# de1_breakout.net
KiCad netlist of a schematic drawn in EAGLE
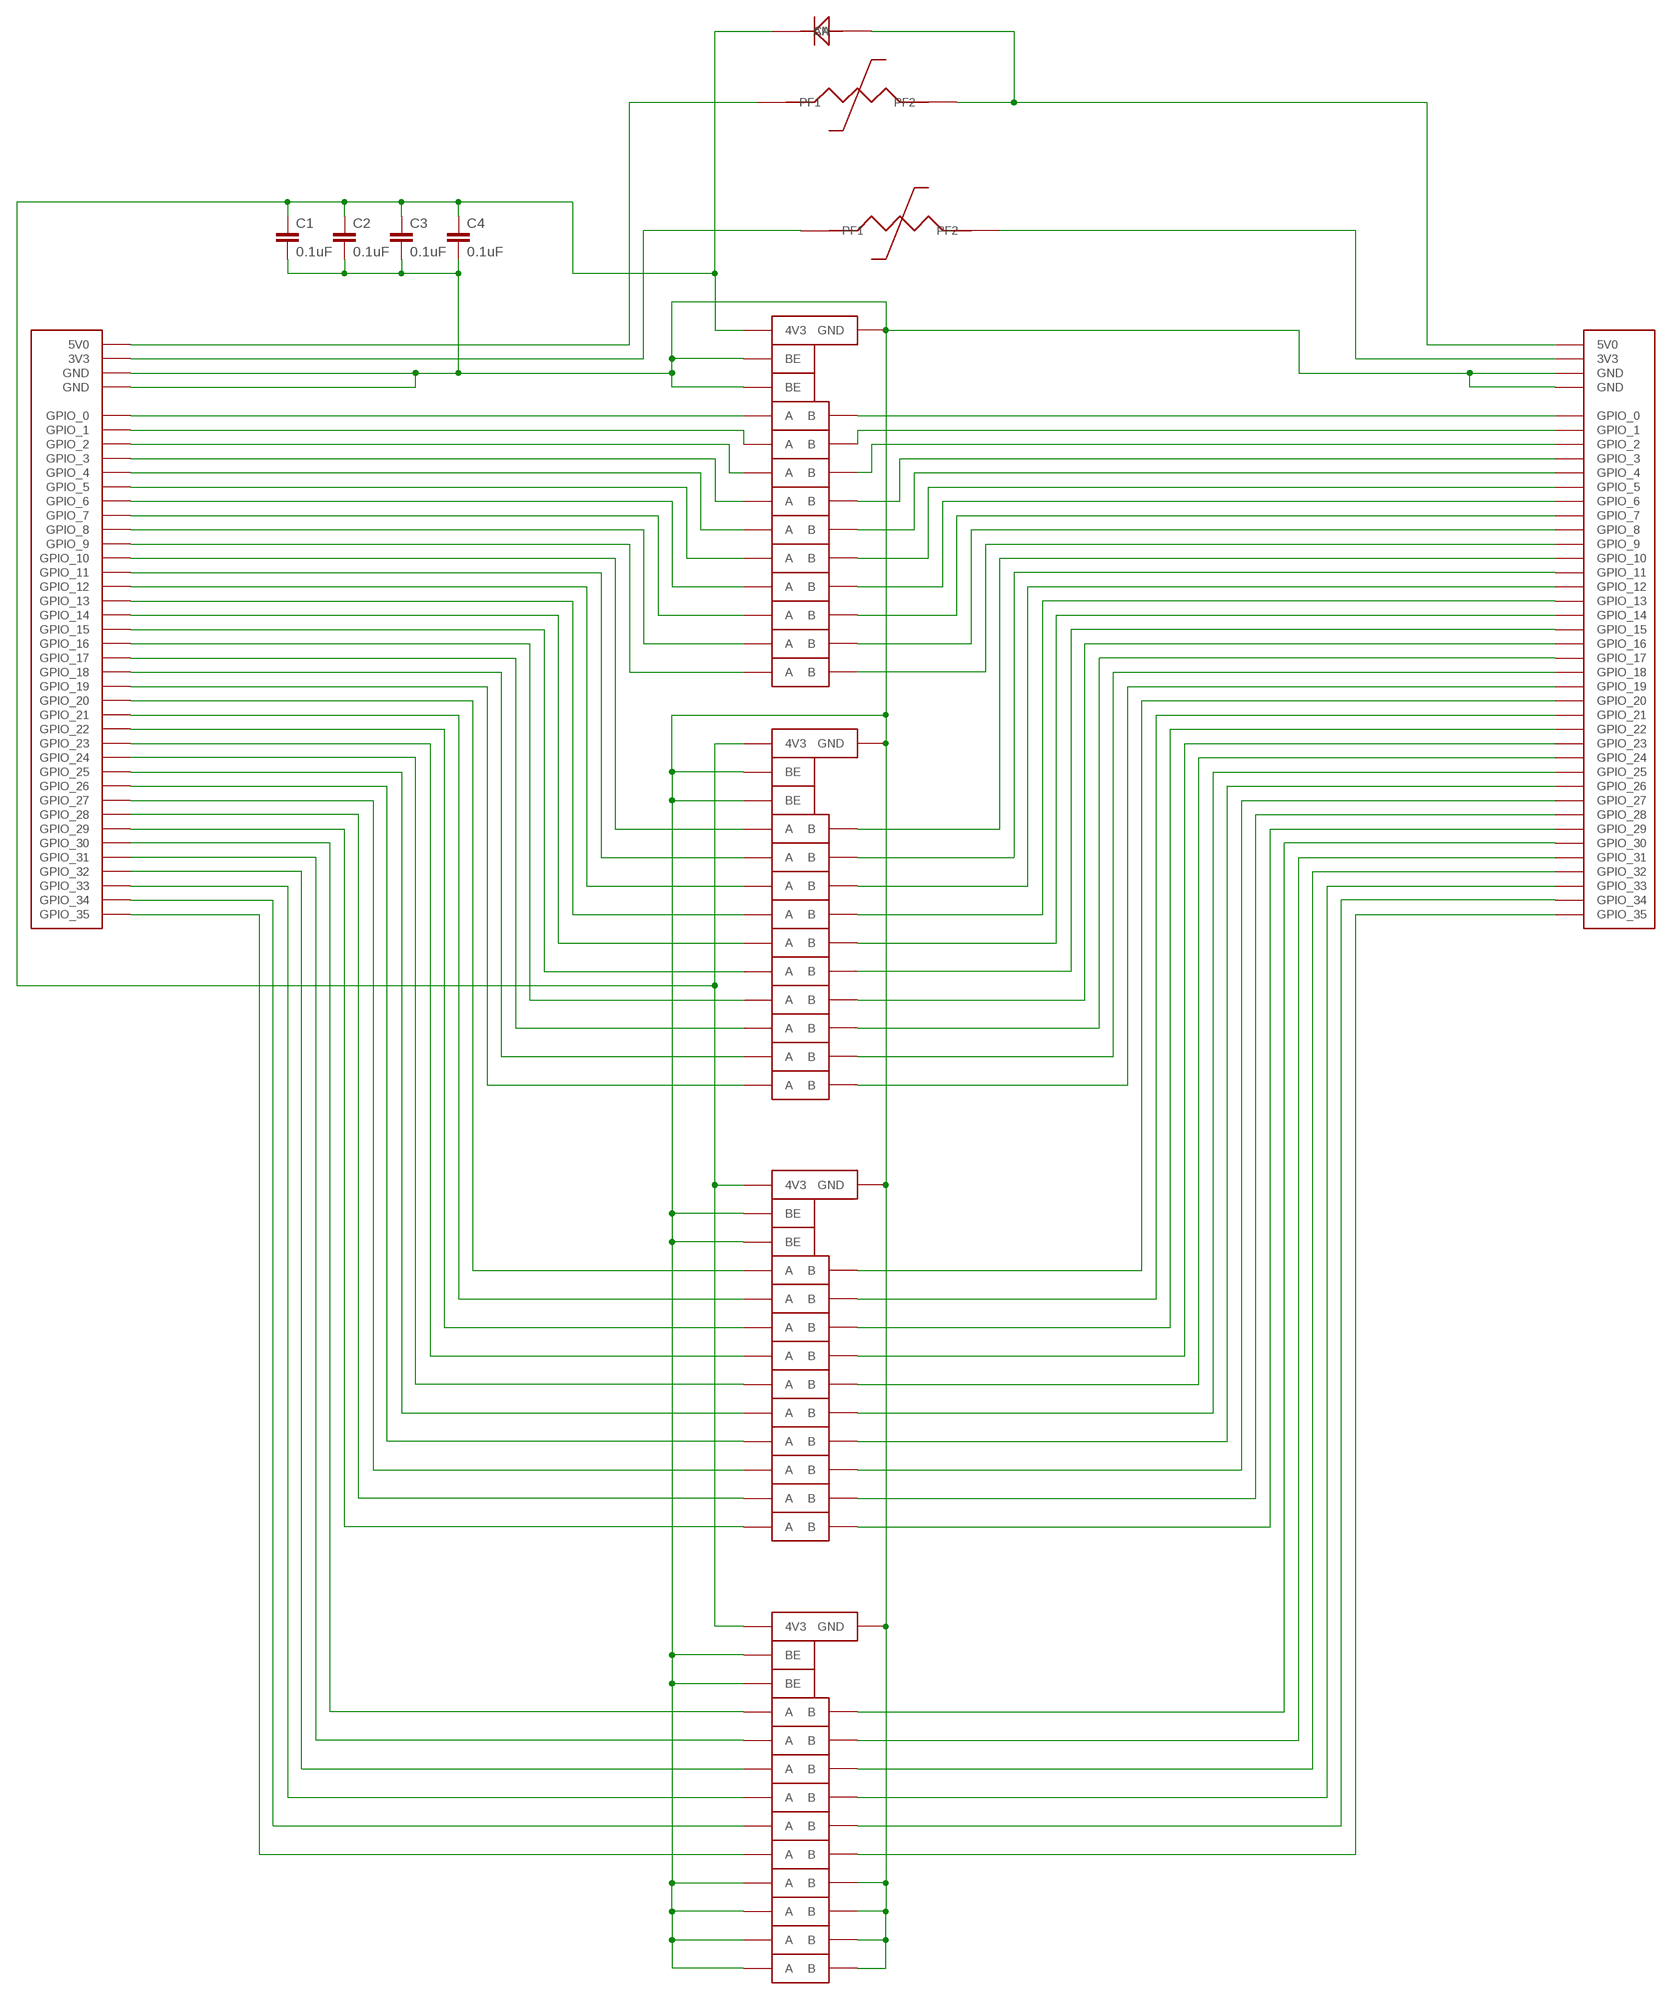
[diagram p0: schematic, sheet 1]

(export (version "E")
  (design (tool "Eeschema 10.0.6"))
  (components
    (comp (ref "1N4148")
      (value "1N4148")
      (footprint "eagle-import:SOD123")
      (libsource (lib "eagle-import") (part "1N4148"))
    )
    (comp (ref "3VPOLY")
      (value "POLYFUSE_1206")
      (footprint "eagle-import:C1206")
      (libsource (lib "eagle-import") (part "POLYFUSE_1206"))
    )
    (comp (ref "5VPOLY")
      (value "POLYFUSE_1206")
      (footprint "eagle-import:C1206")
      (libsource (lib "eagle-import") (part "POLYFUSE_1206"))
    )
    (comp (ref "C1")
      (value "0.1uF")
      (footprint "eagle-import:C1206")
      (libsource (lib "eagle-import") (part "C-EUC1206"))
    )
    (comp (ref "C2")
      (value "0.1uF")
      (footprint "eagle-import:C1206")
      (libsource (lib "eagle-import") (part "C-EUC1206"))
    )
    (comp (ref "C3")
      (value "0.1uF")
      (footprint "eagle-import:C1206")
      (libsource (lib "eagle-import") (part "C-EUC1206"))
    )
    (comp (ref "C4")
      (value "0.1uF")
      (footprint "eagle-import:C1206")
      (libsource (lib "eagle-import") (part "C-EUC1206"))
    )
    (comp (ref "DE1_GPIO")
      (value "DE1_GPIO")
      (footprint "eagle-import:DIL-100-2X20")
      (libsource (lib "eagle-import") (part "DE1_GPIO"))
    )
    (comp (ref "EXT_GPIO")
      (value "DE1_GPIO_L")
      (footprint "eagle-import:DIL-100-2X20")
      (libsource (lib "eagle-import") (part "DE1_GPIO_L"))
    )
    (comp (ref "IC1")
      (value "QS3384")
      (footprint "eagle-import:TSSOP24")
      (libsource (lib "eagle-import") (part "QS3384"))
    )
    (comp (ref "IC2")
      (value "QS3384")
      (footprint "eagle-import:TSSOP24")
      (libsource (lib "eagle-import") (part "QS3384"))
    )
    (comp (ref "IC3")
      (value "QS3384")
      (footprint "eagle-import:TSSOP24")
      (libsource (lib "eagle-import") (part "QS3384"))
    )
    (comp (ref "IC4")
      (value "QS3384")
      (footprint "eagle-import:TSSOP24")
      (libsource (lib "eagle-import") (part "QS3384"))
    )
  )
  (nets
    (net (code "1") (name "Net-(1N4148-AN)") (class "Default")
      (node (ref "1N4148") (pin "2") (pinfunction "AN_2") (pintype "bidirectional"))
      (node (ref "5VPOLY") (pin "2") (pinfunction "PF2_2") (pintype "bidirectional"))
      (node (ref "EXT_GPIO") (pin "11") (pinfunction "5V0_11") (pintype "power_in"))
    )
    (net (code "2") (name "Net-(1N4148-CA)") (class "Default")
      (node (ref "1N4148") (pin "1") (pinfunction "CA_1") (pintype "bidirectional"))
      (node (ref "C1") (pin "1") (pinfunction "1_1") (pintype "passive"))
      (node (ref "C2") (pin "1") (pinfunction "1_1") (pintype "passive"))
      (node (ref "C3") (pin "1") (pinfunction "1_1") (pintype "passive"))
      (node (ref "C4") (pin "1") (pinfunction "1_1") (pintype "passive"))
      (node (ref "IC1") (pin "24") (pinfunction "4V3_24") (pintype "power_in"))
      (node (ref "IC2") (pin "24") (pinfunction "4V3_24") (pintype "power_in"))
      (node (ref "IC3") (pin "24") (pinfunction "4V3_24") (pintype "power_in"))
      (node (ref "IC4") (pin "24") (pinfunction "4V3_24") (pintype "power_in"))
    )
    (net (code "3") (name "Net-(3VPOLY-PF1)") (class "Default")
      (node (ref "3VPOLY") (pin "1") (pinfunction "PF1_1") (pintype "bidirectional"))
      (node (ref "DE1_GPIO") (pin "29") (pinfunction "3V3_29") (pintype "power_in"))
    )
    (net (code "4") (name "Net-(3VPOLY-PF2)") (class "Default")
      (node (ref "3VPOLY") (pin "2") (pinfunction "PF2_2") (pintype "bidirectional"))
      (node (ref "EXT_GPIO") (pin "29") (pinfunction "3V3_29") (pintype "power_in"))
    )
    (net (code "5") (name "Net-(5VPOLY-PF1)") (class "Default")
      (node (ref "5VPOLY") (pin "1") (pinfunction "PF1_1") (pintype "bidirectional"))
      (node (ref "DE1_GPIO") (pin "11") (pinfunction "5V0_11") (pintype "power_in"))
    )
    (net (code "6") (name "Net-(DE1_GPIO-GPIO_0)") (class "Default")
      (node (ref "DE1_GPIO") (pin "1") (pinfunction "GPIO_0_1") (pintype "bidirectional"))
      (node (ref "IC1") (pin "3") (pinfunction "A_3") (pintype "input"))
    )
    (net (code "7") (name "Net-(DE1_GPIO-GPIO_1)") (class "Default")
      (node (ref "DE1_GPIO") (pin "2") (pinfunction "GPIO_1_2") (pintype "bidirectional"))
      (node (ref "IC1") (pin "4") (pinfunction "A_4") (pintype "input"))
    )
    (net (code "8") (name "Net-(DE1_GPIO-GPIO_2)") (class "Default")
      (node (ref "DE1_GPIO") (pin "3") (pinfunction "GPIO_2_3") (pintype "bidirectional"))
      (node (ref "IC1") (pin "7") (pinfunction "A_7") (pintype "input"))
    )
    (net (code "9") (name "Net-(DE1_GPIO-GPIO_3)") (class "Default")
      (node (ref "DE1_GPIO") (pin "4") (pinfunction "GPIO_3_4") (pintype "bidirectional"))
      (node (ref "IC1") (pin "8") (pinfunction "A_8") (pintype "input"))
    )
    (net (code "10") (name "Net-(DE1_GPIO-GPIO_4)") (class "Default")
      (node (ref "DE1_GPIO") (pin "5") (pinfunction "GPIO_4_5") (pintype "bidirectional"))
      (node (ref "IC1") (pin "11") (pinfunction "A_11") (pintype "input"))
    )
    (net (code "11") (name "Net-(DE1_GPIO-GPIO_5)") (class "Default")
      (node (ref "DE1_GPIO") (pin "6") (pinfunction "GPIO_5_6") (pintype "bidirectional"))
      (node (ref "IC1") (pin "14") (pinfunction "A_14") (pintype "input"))
    )
    (net (code "12") (name "Net-(DE1_GPIO-GPIO_6)") (class "Default")
      (node (ref "DE1_GPIO") (pin "7") (pinfunction "GPIO_6_7") (pintype "bidirectional"))
      (node (ref "IC1") (pin "17") (pinfunction "A_17") (pintype "input"))
    )
    (net (code "13") (name "Net-(DE1_GPIO-GPIO_7)") (class "Default")
      (node (ref "DE1_GPIO") (pin "8") (pinfunction "GPIO_7_8") (pintype "bidirectional"))
      (node (ref "IC1") (pin "18") (pinfunction "A_18") (pintype "input"))
    )
    (net (code "14") (name "Net-(DE1_GPIO-GPIO_8)") (class "Default")
      (node (ref "DE1_GPIO") (pin "9") (pinfunction "GPIO_8_9") (pintype "bidirectional"))
      (node (ref "IC1") (pin "21") (pinfunction "A_21") (pintype "input"))
    )
    (net (code "15") (name "Net-(DE1_GPIO-GPIO_9)") (class "Default")
      (node (ref "DE1_GPIO") (pin "10") (pinfunction "GPIO_9_10") (pintype "bidirectional"))
      (node (ref "IC1") (pin "22") (pinfunction "A_22") (pintype "input"))
    )
    (net (code "16") (name "Net-(DE1_GPIO-GPIO_10)") (class "Default")
      (node (ref "DE1_GPIO") (pin "13") (pinfunction "GPIO_10_13") (pintype "bidirectional"))
      (node (ref "IC2") (pin "3") (pinfunction "A_3") (pintype "input"))
    )
    (net (code "17") (name "Net-(DE1_GPIO-GPIO_11)") (class "Default")
      (node (ref "DE1_GPIO") (pin "14") (pinfunction "GPIO_11_14") (pintype "bidirectional"))
      (node (ref "IC2") (pin "4") (pinfunction "A_4") (pintype "input"))
    )
    (net (code "18") (name "Net-(DE1_GPIO-GPIO_12)") (class "Default")
      (node (ref "DE1_GPIO") (pin "15") (pinfunction "GPIO_12_15") (pintype "bidirectional"))
      (node (ref "IC2") (pin "7") (pinfunction "A_7") (pintype "input"))
    )
    (net (code "19") (name "Net-(DE1_GPIO-GPIO_13)") (class "Default")
      (node (ref "DE1_GPIO") (pin "16") (pinfunction "GPIO_13_16") (pintype "bidirectional"))
      (node (ref "IC2") (pin "8") (pinfunction "A_8") (pintype "input"))
    )
    (net (code "20") (name "Net-(DE1_GPIO-GPIO_14)") (class "Default")
      (node (ref "DE1_GPIO") (pin "17") (pinfunction "GPIO_14_17") (pintype "bidirectional"))
      (node (ref "IC2") (pin "11") (pinfunction "A_11") (pintype "input"))
    )
    (net (code "21") (name "Net-(DE1_GPIO-GPIO_15)") (class "Default")
      (node (ref "DE1_GPIO") (pin "18") (pinfunction "GPIO_15_18") (pintype "bidirectional"))
      (node (ref "IC2") (pin "14") (pinfunction "A_14") (pintype "input"))
    )
    (net (code "22") (name "Net-(DE1_GPIO-GPIO_16)") (class "Default")
      (node (ref "DE1_GPIO") (pin "19") (pinfunction "GPIO_16_19") (pintype "bidirectional"))
      (node (ref "IC2") (pin "17") (pinfunction "A_17") (pintype "input"))
    )
    (net (code "23") (name "Net-(DE1_GPIO-GPIO_17)") (class "Default")
      (node (ref "DE1_GPIO") (pin "20") (pinfunction "GPIO_17_20") (pintype "bidirectional"))
      (node (ref "IC2") (pin "18") (pinfunction "A_18") (pintype "input"))
    )
    (net (code "24") (name "Net-(DE1_GPIO-GPIO_18)") (class "Default")
      (node (ref "DE1_GPIO") (pin "21") (pinfunction "GPIO_18_21") (pintype "bidirectional"))
      (node (ref "IC2") (pin "21") (pinfunction "A_21") (pintype "input"))
    )
    (net (code "25") (name "Net-(DE1_GPIO-GPIO_19)") (class "Default")
      (node (ref "DE1_GPIO") (pin "22") (pinfunction "GPIO_19_22") (pintype "bidirectional"))
      (node (ref "IC2") (pin "22") (pinfunction "A_22") (pintype "input"))
    )
    (net (code "26") (name "Net-(DE1_GPIO-GPIO_20)") (class "Default")
      (node (ref "DE1_GPIO") (pin "23") (pinfunction "GPIO_20_23") (pintype "bidirectional"))
      (node (ref "IC3") (pin "3") (pinfunction "A_3") (pintype "input"))
    )
    (net (code "27") (name "Net-(DE1_GPIO-GPIO_21)") (class "Default")
      (node (ref "DE1_GPIO") (pin "24") (pinfunction "GPIO_21_24") (pintype "bidirectional"))
      (node (ref "IC3") (pin "4") (pinfunction "A_4") (pintype "input"))
    )
    (net (code "28") (name "Net-(DE1_GPIO-GPIO_22)") (class "Default")
      (node (ref "DE1_GPIO") (pin "25") (pinfunction "GPIO_22_25") (pintype "bidirectional"))
      (node (ref "IC3") (pin "7") (pinfunction "A_7") (pintype "input"))
    )
    (net (code "29") (name "Net-(DE1_GPIO-GPIO_23)") (class "Default")
      (node (ref "DE1_GPIO") (pin "26") (pinfunction "GPIO_23_26") (pintype "bidirectional"))
      (node (ref "IC3") (pin "8") (pinfunction "A_8") (pintype "input"))
    )
    (net (code "30") (name "Net-(DE1_GPIO-GPIO_24)") (class "Default")
      (node (ref "DE1_GPIO") (pin "27") (pinfunction "GPIO_24_27") (pintype "bidirectional"))
      (node (ref "IC3") (pin "11") (pinfunction "A_11") (pintype "input"))
    )
    (net (code "31") (name "Net-(DE1_GPIO-GPIO_25)") (class "Default")
      (node (ref "DE1_GPIO") (pin "28") (pinfunction "GPIO_25_28") (pintype "bidirectional"))
      (node (ref "IC3") (pin "14") (pinfunction "A_14") (pintype "input"))
    )
    (net (code "32") (name "Net-(DE1_GPIO-GPIO_26)") (class "Default")
      (node (ref "DE1_GPIO") (pin "31") (pinfunction "GPIO_26_31") (pintype "bidirectional"))
      (node (ref "IC3") (pin "17") (pinfunction "A_17") (pintype "input"))
    )
    (net (code "33") (name "Net-(DE1_GPIO-GPIO_27)") (class "Default")
      (node (ref "DE1_GPIO") (pin "32") (pinfunction "GPIO_27_32") (pintype "bidirectional"))
      (node (ref "IC3") (pin "18") (pinfunction "A_18") (pintype "input"))
    )
    (net (code "34") (name "Net-(DE1_GPIO-GPIO_28)") (class "Default")
      (node (ref "DE1_GPIO") (pin "33") (pinfunction "GPIO_28_33") (pintype "bidirectional"))
      (node (ref "IC3") (pin "21") (pinfunction "A_21") (pintype "input"))
    )
    (net (code "35") (name "Net-(DE1_GPIO-GPIO_29)") (class "Default")
      (node (ref "DE1_GPIO") (pin "34") (pinfunction "GPIO_29_34") (pintype "bidirectional"))
      (node (ref "IC3") (pin "22") (pinfunction "A_22") (pintype "input"))
    )
    (net (code "36") (name "Net-(DE1_GPIO-GPIO_30)") (class "Default")
      (node (ref "DE1_GPIO") (pin "35") (pinfunction "GPIO_30_35") (pintype "bidirectional"))
      (node (ref "IC4") (pin "3") (pinfunction "A_3") (pintype "input"))
    )
    (net (code "37") (name "Net-(DE1_GPIO-GPIO_31)") (class "Default")
      (node (ref "DE1_GPIO") (pin "36") (pinfunction "GPIO_31_36") (pintype "bidirectional"))
      (node (ref "IC4") (pin "4") (pinfunction "A_4") (pintype "input"))
    )
    (net (code "38") (name "Net-(DE1_GPIO-GPIO_32)") (class "Default")
      (node (ref "DE1_GPIO") (pin "37") (pinfunction "GPIO_32_37") (pintype "bidirectional"))
      (node (ref "IC4") (pin "7") (pinfunction "A_7") (pintype "input"))
    )
    (net (code "39") (name "Net-(DE1_GPIO-GPIO_33)") (class "Default")
      (node (ref "DE1_GPIO") (pin "38") (pinfunction "GPIO_33_38") (pintype "bidirectional"))
      (node (ref "IC4") (pin "8") (pinfunction "A_8") (pintype "input"))
    )
    (net (code "40") (name "Net-(DE1_GPIO-GPIO_34)") (class "Default")
      (node (ref "DE1_GPIO") (pin "39") (pinfunction "GPIO_34_39") (pintype "bidirectional"))
      (node (ref "IC4") (pin "11") (pinfunction "A_11") (pintype "input"))
    )
    (net (code "41") (name "Net-(DE1_GPIO-GPIO_35)") (class "Default")
      (node (ref "DE1_GPIO") (pin "40") (pinfunction "GPIO_35_40") (pintype "bidirectional"))
      (node (ref "IC4") (pin "14") (pinfunction "A_14") (pintype "input"))
    )
    (net (code "42") (name "Net-(EXT_GPIO-GPIO_0)") (class "Default")
      (node (ref "EXT_GPIO") (pin "1") (pinfunction "GPIO_0_1") (pintype "bidirectional"))
      (node (ref "IC1") (pin "2") (pinfunction "B_2") (pintype "input"))
    )
    (net (code "43") (name "Net-(EXT_GPIO-GPIO_1)") (class "Default")
      (node (ref "EXT_GPIO") (pin "2") (pinfunction "GPIO_1_2") (pintype "bidirectional"))
      (node (ref "IC1") (pin "5") (pinfunction "B_5") (pintype "input"))
    )
    (net (code "44") (name "Net-(EXT_GPIO-GPIO_2)") (class "Default")
      (node (ref "EXT_GPIO") (pin "3") (pinfunction "GPIO_2_3") (pintype "bidirectional"))
      (node (ref "IC1") (pin "6") (pinfunction "B_6") (pintype "input"))
    )
    (net (code "45") (name "Net-(EXT_GPIO-GPIO_3)") (class "Default")
      (node (ref "EXT_GPIO") (pin "4") (pinfunction "GPIO_3_4") (pintype "bidirectional"))
      (node (ref "IC1") (pin "9") (pinfunction "B_9") (pintype "input"))
    )
    (net (code "46") (name "Net-(EXT_GPIO-GPIO_4)") (class "Default")
      (node (ref "EXT_GPIO") (pin "5") (pinfunction "GPIO_4_5") (pintype "bidirectional"))
      (node (ref "IC1") (pin "10") (pinfunction "B_10") (pintype "input"))
    )
    (net (code "47") (name "Net-(EXT_GPIO-GPIO_5)") (class "Default")
      (node (ref "EXT_GPIO") (pin "6") (pinfunction "GPIO_5_6") (pintype "bidirectional"))
      (node (ref "IC1") (pin "15") (pinfunction "B_15") (pintype "input"))
    )
    (net (code "48") (name "Net-(EXT_GPIO-GPIO_6)") (class "Default")
      (node (ref "EXT_GPIO") (pin "7") (pinfunction "GPIO_6_7") (pintype "bidirectional"))
      (node (ref "IC1") (pin "16") (pinfunction "B_16") (pintype "input"))
    )
    (net (code "49") (name "Net-(EXT_GPIO-GPIO_7)") (class "Default")
      (node (ref "EXT_GPIO") (pin "8") (pinfunction "GPIO_7_8") (pintype "bidirectional"))
      (node (ref "IC1") (pin "19") (pinfunction "B_19") (pintype "input"))
    )
    (net (code "50") (name "Net-(EXT_GPIO-GPIO_8)") (class "Default")
      (node (ref "EXT_GPIO") (pin "9") (pinfunction "GPIO_8_9") (pintype "bidirectional"))
      (node (ref "IC1") (pin "20") (pinfunction "B_20") (pintype "input"))
    )
    (net (code "51") (name "Net-(EXT_GPIO-GPIO_9)") (class "Default")
      (node (ref "EXT_GPIO") (pin "10") (pinfunction "GPIO_9_10") (pintype "bidirectional"))
      (node (ref "IC1") (pin "23") (pinfunction "B_23") (pintype "input"))
    )
    (net (code "52") (name "Net-(EXT_GPIO-GPIO_10)") (class "Default")
      (node (ref "EXT_GPIO") (pin "13") (pinfunction "GPIO_10_13") (pintype "bidirectional"))
      (node (ref "IC2") (pin "2") (pinfunction "B_2") (pintype "input"))
    )
    (net (code "53") (name "Net-(EXT_GPIO-GPIO_11)") (class "Default")
      (node (ref "EXT_GPIO") (pin "14") (pinfunction "GPIO_11_14") (pintype "bidirectional"))
      (node (ref "IC2") (pin "5") (pinfunction "B_5") (pintype "input"))
    )
    (net (code "54") (name "Net-(EXT_GPIO-GPIO_12)") (class "Default")
      (node (ref "EXT_GPIO") (pin "15") (pinfunction "GPIO_12_15") (pintype "bidirectional"))
      (node (ref "IC2") (pin "6") (pinfunction "B_6") (pintype "input"))
    )
    (net (code "55") (name "Net-(EXT_GPIO-GPIO_13)") (class "Default")
      (node (ref "EXT_GPIO") (pin "16") (pinfunction "GPIO_13_16") (pintype "bidirectional"))
      (node (ref "IC2") (pin "9") (pinfunction "B_9") (pintype "input"))
    )
    (net (code "56") (name "Net-(EXT_GPIO-GPIO_14)") (class "Default")
      (node (ref "EXT_GPIO") (pin "17") (pinfunction "GPIO_14_17") (pintype "bidirectional"))
      (node (ref "IC2") (pin "10") (pinfunction "B_10") (pintype "input"))
    )
    (net (code "57") (name "Net-(EXT_GPIO-GPIO_15)") (class "Default")
      (node (ref "EXT_GPIO") (pin "18") (pinfunction "GPIO_15_18") (pintype "bidirectional"))
      (node (ref "IC2") (pin "15") (pinfunction "B_15") (pintype "input"))
    )
    (net (code "58") (name "Net-(EXT_GPIO-GPIO_16)") (class "Default")
      (node (ref "EXT_GPIO") (pin "19") (pinfunction "GPIO_16_19") (pintype "bidirectional"))
      (node (ref "IC2") (pin "16") (pinfunction "B_16") (pintype "input"))
    )
    (net (code "59") (name "Net-(EXT_GPIO-GPIO_17)") (class "Default")
      (node (ref "EXT_GPIO") (pin "20") (pinfunction "GPIO_17_20") (pintype "bidirectional"))
      (node (ref "IC2") (pin "19") (pinfunction "B_19") (pintype "input"))
    )
    (net (code "60") (name "Net-(EXT_GPIO-GPIO_18)") (class "Default")
      (node (ref "EXT_GPIO") (pin "21") (pinfunction "GPIO_18_21") (pintype "bidirectional"))
      (node (ref "IC2") (pin "20") (pinfunction "B_20") (pintype "input"))
    )
    (net (code "61") (name "Net-(EXT_GPIO-GPIO_19)") (class "Default")
      (node (ref "EXT_GPIO") (pin "22") (pinfunction "GPIO_19_22") (pintype "bidirectional"))
      (node (ref "IC2") (pin "23") (pinfunction "B_23") (pintype "input"))
    )
    (net (code "62") (name "Net-(EXT_GPIO-GPIO_20)") (class "Default")
      (node (ref "EXT_GPIO") (pin "23") (pinfunction "GPIO_20_23") (pintype "bidirectional"))
      (node (ref "IC3") (pin "2") (pinfunction "B_2") (pintype "input"))
    )
    (net (code "63") (name "Net-(EXT_GPIO-GPIO_21)") (class "Default")
      (node (ref "EXT_GPIO") (pin "24") (pinfunction "GPIO_21_24") (pintype "bidirectional"))
      (node (ref "IC3") (pin "5") (pinfunction "B_5") (pintype "input"))
    )
    (net (code "64") (name "Net-(EXT_GPIO-GPIO_22)") (class "Default")
      (node (ref "EXT_GPIO") (pin "25") (pinfunction "GPIO_22_25") (pintype "bidirectional"))
      (node (ref "IC3") (pin "6") (pinfunction "B_6") (pintype "input"))
    )
    (net (code "65") (name "Net-(EXT_GPIO-GPIO_23)") (class "Default")
      (node (ref "EXT_GPIO") (pin "26") (pinfunction "GPIO_23_26") (pintype "bidirectional"))
      (node (ref "IC3") (pin "9") (pinfunction "B_9") (pintype "input"))
    )
    (net (code "66") (name "Net-(EXT_GPIO-GPIO_24)") (class "Default")
      (node (ref "EXT_GPIO") (pin "27") (pinfunction "GPIO_24_27") (pintype "bidirectional"))
      (node (ref "IC3") (pin "10") (pinfunction "B_10") (pintype "input"))
    )
    (net (code "67") (name "Net-(EXT_GPIO-GPIO_25)") (class "Default")
      (node (ref "EXT_GPIO") (pin "28") (pinfunction "GPIO_25_28") (pintype "bidirectional"))
      (node (ref "IC3") (pin "15") (pinfunction "B_15") (pintype "input"))
    )
    (net (code "68") (name "Net-(EXT_GPIO-GPIO_26)") (class "Default")
      (node (ref "EXT_GPIO") (pin "31") (pinfunction "GPIO_26_31") (pintype "bidirectional"))
      (node (ref "IC3") (pin "16") (pinfunction "B_16") (pintype "input"))
    )
    (net (code "69") (name "Net-(EXT_GPIO-GPIO_27)") (class "Default")
      (node (ref "EXT_GPIO") (pin "32") (pinfunction "GPIO_27_32") (pintype "bidirectional"))
      (node (ref "IC3") (pin "19") (pinfunction "B_19") (pintype "input"))
    )
    (net (code "70") (name "Net-(EXT_GPIO-GPIO_28)") (class "Default")
      (node (ref "EXT_GPIO") (pin "33") (pinfunction "GPIO_28_33") (pintype "bidirectional"))
      (node (ref "IC3") (pin "20") (pinfunction "B_20") (pintype "input"))
    )
    (net (code "71") (name "Net-(EXT_GPIO-GPIO_29)") (class "Default")
      (node (ref "EXT_GPIO") (pin "34") (pinfunction "GPIO_29_34") (pintype "bidirectional"))
      (node (ref "IC3") (pin "23") (pinfunction "B_23") (pintype "input"))
    )
    (net (code "72") (name "Net-(EXT_GPIO-GPIO_30)") (class "Default")
      (node (ref "EXT_GPIO") (pin "35") (pinfunction "GPIO_30_35") (pintype "bidirectional"))
      (node (ref "IC4") (pin "2") (pinfunction "B_2") (pintype "input"))
    )
    (net (code "73") (name "Net-(EXT_GPIO-GPIO_31)") (class "Default")
      (node (ref "EXT_GPIO") (pin "36") (pinfunction "GPIO_31_36") (pintype "bidirectional"))
      (node (ref "IC4") (pin "5") (pinfunction "B_5") (pintype "input"))
    )
    (net (code "74") (name "Net-(EXT_GPIO-GPIO_32)") (class "Default")
      (node (ref "EXT_GPIO") (pin "37") (pinfunction "GPIO_32_37") (pintype "bidirectional"))
      (node (ref "IC4") (pin "6") (pinfunction "B_6") (pintype "input"))
    )
    (net (code "75") (name "Net-(EXT_GPIO-GPIO_33)") (class "Default")
      (node (ref "EXT_GPIO") (pin "38") (pinfunction "GPIO_33_38") (pintype "bidirectional"))
      (node (ref "IC4") (pin "9") (pinfunction "B_9") (pintype "input"))
    )
    (net (code "76") (name "Net-(EXT_GPIO-GPIO_34)") (class "Default")
      (node (ref "EXT_GPIO") (pin "39") (pinfunction "GPIO_34_39") (pintype "bidirectional"))
      (node (ref "IC4") (pin "10") (pinfunction "B_10") (pintype "input"))
    )
    (net (code "77") (name "Net-(EXT_GPIO-GPIO_35)") (class "Default")
      (node (ref "EXT_GPIO") (pin "40") (pinfunction "GPIO_35_40") (pintype "bidirectional"))
      (node (ref "IC4") (pin "15") (pinfunction "B_15") (pintype "input"))
    )
    (net (code "78") (name "Net-(IC1A-BE)") (class "Default")
      (node (ref "C1") (pin "2") (pinfunction "2_2") (pintype "passive"))
      (node (ref "C2") (pin "2") (pinfunction "2_2") (pintype "passive"))
      (node (ref "C3") (pin "2") (pinfunction "2_2") (pintype "passive"))
      (node (ref "C4") (pin "2") (pinfunction "2_2") (pintype "passive"))
      (node (ref "DE1_GPIO") (pin "12") (pinfunction "GND_12") (pintype "power_in"))
      (node (ref "DE1_GPIO") (pin "30") (pinfunction "GND_30") (pintype "power_in"))
      (node (ref "EXT_GPIO") (pin "12") (pinfunction "GND_12") (pintype "power_in"))
      (node (ref "EXT_GPIO") (pin "30") (pinfunction "GND_30") (pintype "power_in"))
      (node (ref "IC1") (pin "1") (pinfunction "BE_1") (pintype "input"))
      (node (ref "IC1") (pin "12") (pinfunction "GND_12") (pintype "power_in"))
      (node (ref "IC1") (pin "13") (pinfunction "BE_13") (pintype "input"))
      (node (ref "IC2") (pin "1") (pinfunction "BE_1") (pintype "input"))
      (node (ref "IC2") (pin "12") (pinfunction "GND_12") (pintype "power_in"))
      (node (ref "IC2") (pin "13") (pinfunction "BE_13") (pintype "input"))
      (node (ref "IC3") (pin "1") (pinfunction "BE_1") (pintype "input"))
      (node (ref "IC3") (pin "12") (pinfunction "GND_12") (pintype "power_in"))
      (node (ref "IC3") (pin "13") (pinfunction "BE_13") (pintype "input"))
      (node (ref "IC4") (pin "1") (pinfunction "BE_1") (pintype "input"))
      (node (ref "IC4") (pin "12") (pinfunction "GND_12") (pintype "power_in"))
      (node (ref "IC4") (pin "13") (pinfunction "BE_13") (pintype "input"))
      (node (ref "IC4") (pin "16") (pinfunction "B_16") (pintype "input"))
      (node (ref "IC4") (pin "17") (pinfunction "A_17") (pintype "input"))
      (node (ref "IC4") (pin "18") (pinfunction "A_18") (pintype "input"))
      (node (ref "IC4") (pin "19") (pinfunction "B_19") (pintype "input"))
      (node (ref "IC4") (pin "20") (pinfunction "B_20") (pintype "input"))
      (node (ref "IC4") (pin "21") (pinfunction "A_21") (pintype "input"))
      (node (ref "IC4") (pin "22") (pinfunction "A_22") (pintype "input"))
      (node (ref "IC4") (pin "23") (pinfunction "B_23") (pintype "input"))
    )
  )
)
